# STM32.net
KiCad netlist of a schematic drawn in Altium Designer
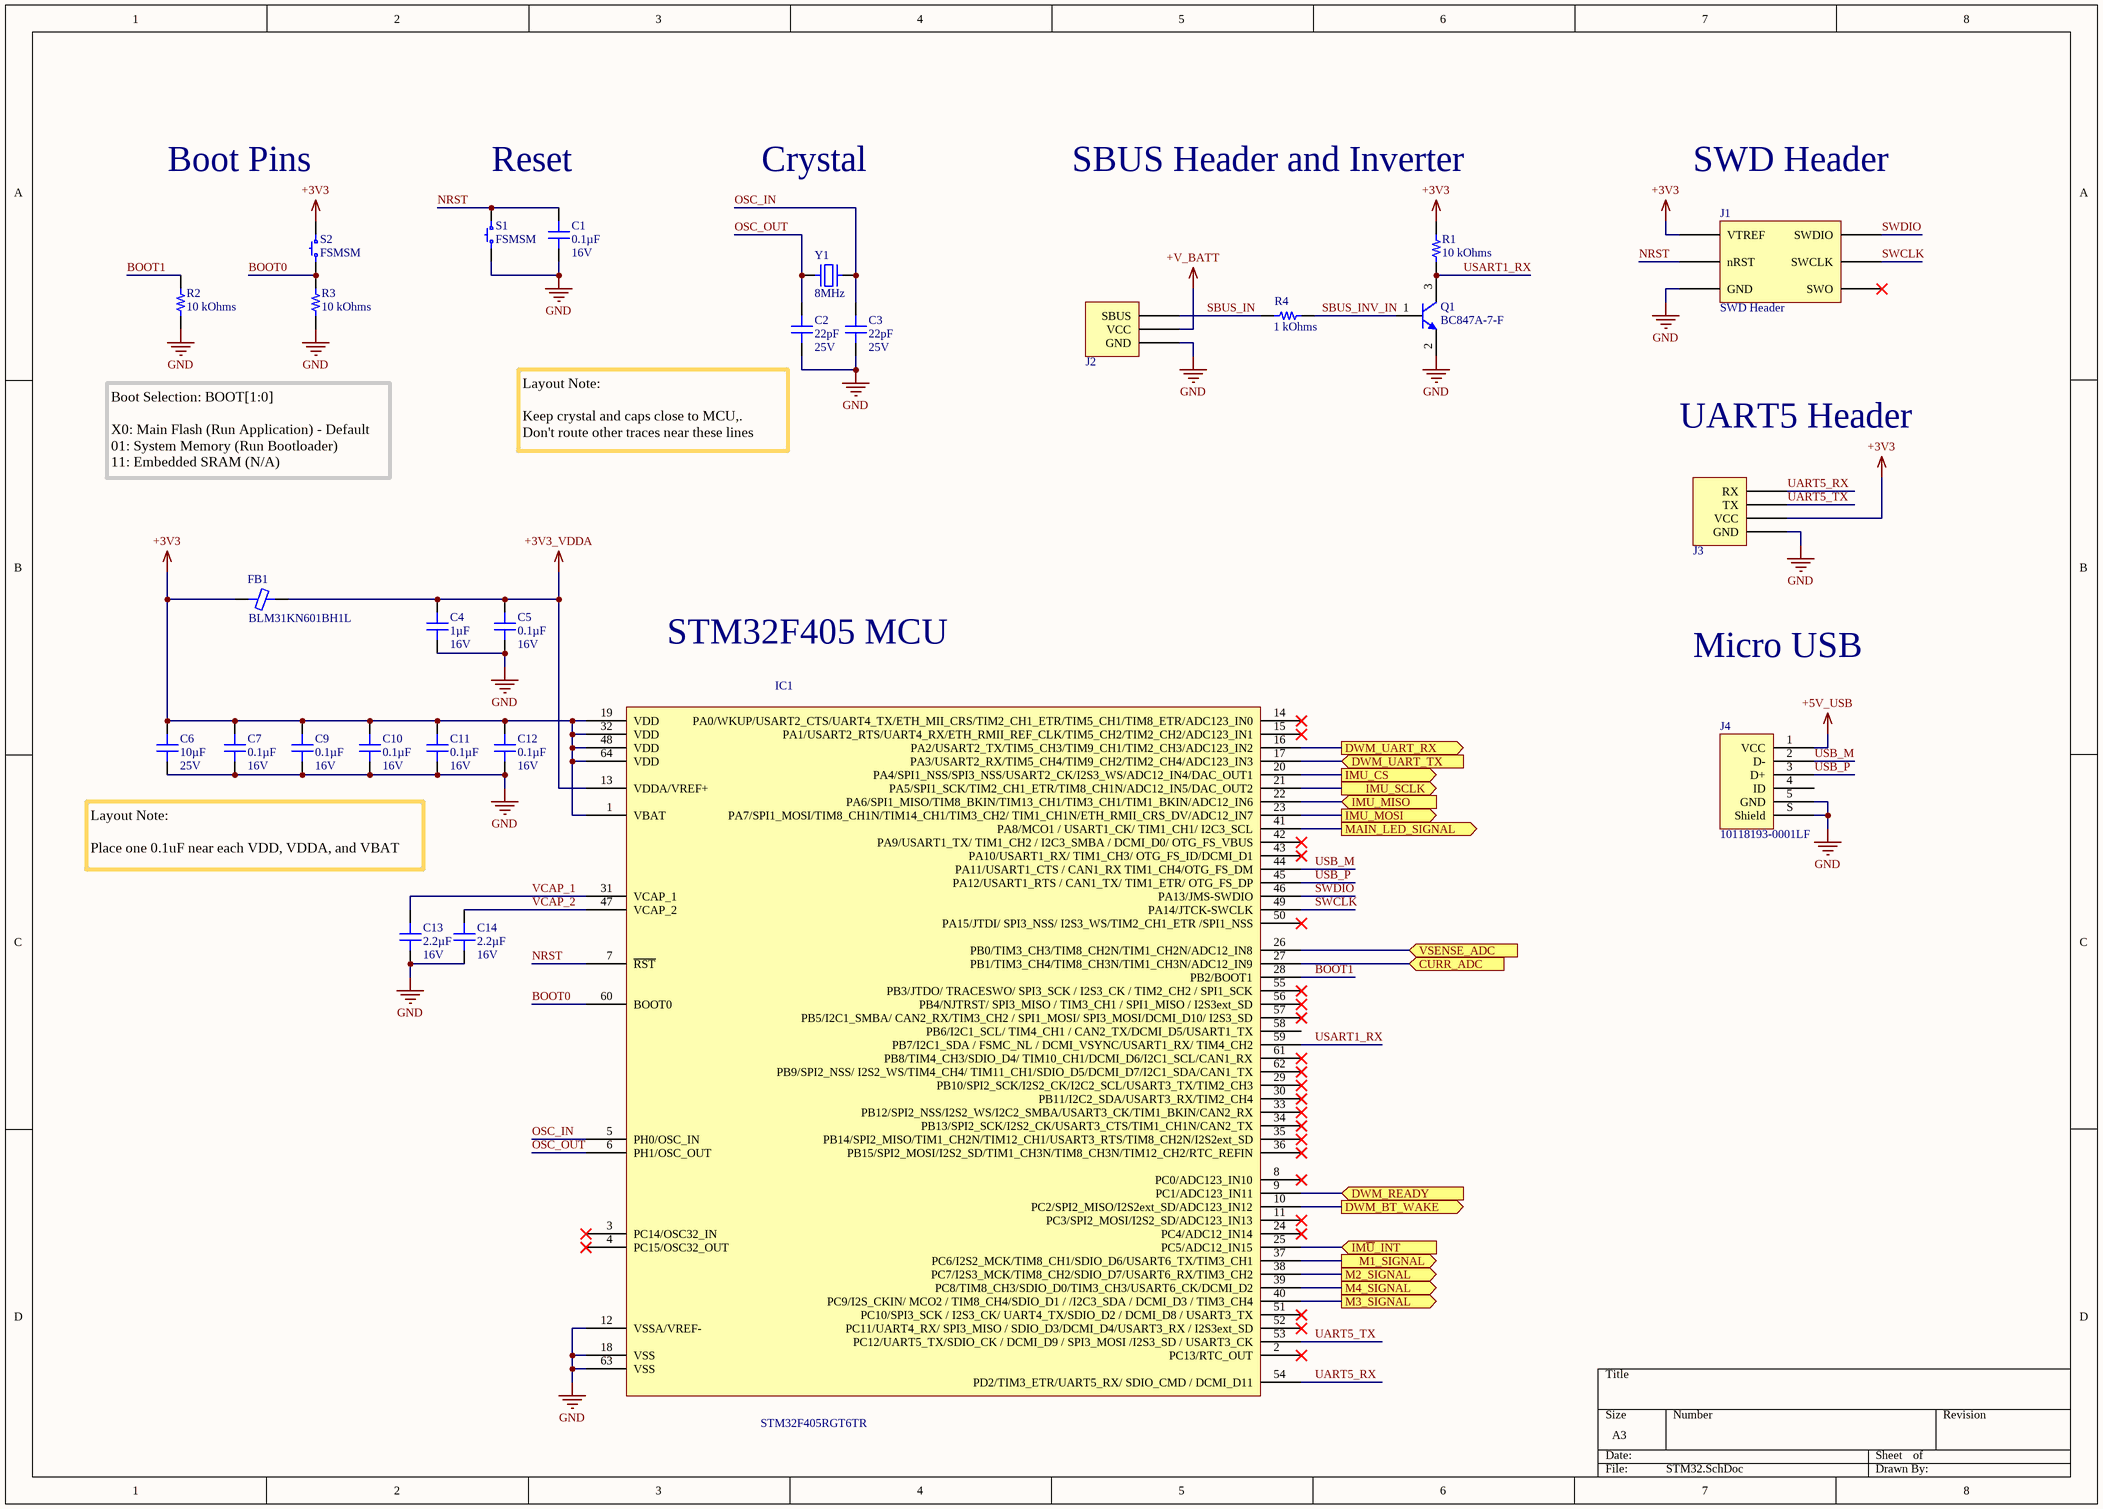
[diagram p0: STM32.SchDoc]

(export (version "E")
  (design (tool "Eeschema 10.0.6"))
  (components
    (comp (ref "C1")
      (value "0.1µF")
      (footprint "CAP 0603_1608")
      (description "CAP CER 0.1UF 16V X7R 0603")
      (fields
        (field (name "PART NUMBER") "CC0603KRX7R7BB104")
        (field (name "MANUFACTURER") "Yageo")
        (field (name "VOLTAGE - RATED") "16V")
      )
      (libsource (lib "Celestial Altium Library - altium_library") (part "Capacitor"))
    )
    (comp (ref "C2")
      (value "22pF")
      (footprint "CAP 0603_1608")
      (description "CAP CER 22PF 25V NPO 0603")
      (fields
        (field (name "PART NUMBER") "CC0603JRNPO8BN220")
        (field (name "MANUFACTURER") "Yageo")
        (field (name "VOLTAGE - RATED") "25V")
      )
      (libsource (lib "Celestial Altium Library - altium_library") (part "Capacitor"))
    )
    (comp (ref "C3")
      (value "22pF")
      (footprint "CAP 0603_1608")
      (description "CAP CER 22PF 25V NPO 0603")
      (fields
        (field (name "PART NUMBER") "CC0603JRNPO8BN220")
        (field (name "MANUFACTURER") "Yageo")
        (field (name "VOLTAGE - RATED") "25V")
      )
      (libsource (lib "Celestial Altium Library - altium_library") (part "Capacitor"))
    )
    (comp (ref "C4")
      (value "1µF")
      (footprint "CAP 0603_1608")
      (description "CAP CER 1UF 16V X5R 0603")
      (fields
        (field (name "PART NUMBER") "CC0603MRX5R7BB105")
        (field (name "MANUFACTURER") "Yageo")
        (field (name "VOLTAGE - RATED") "16V")
      )
      (libsource (lib "Celestial Altium Library - altium_library") (part "Capacitor"))
    )
    (comp (ref "C5")
      (value "0.1µF")
      (footprint "CAP 0603_1608")
      (description "CAP CER 0.1UF 16V X7R 0603")
      (fields
        (field (name "PART NUMBER") "CC0603KRX7R7BB104")
        (field (name "MANUFACTURER") "Yageo")
        (field (name "VOLTAGE - RATED") "16V")
      )
      (libsource (lib "Celestial Altium Library - altium_library") (part "Capacitor"))
    )
    (comp (ref "C6")
      (value "10µF")
      (footprint "CAP 0603_1608")
      (description "CAP CER 10UF 25V X5R 0603")
      (fields
        (field (name "PART NUMBER") "CC0603MRX5R8BB106")
        (field (name "MANUFACTURER") "Yageo")
        (field (name "VOLTAGE - RATED") "25V")
      )
      (libsource (lib "Celestial Altium Library - altium_library") (part "Capacitor"))
    )
    (comp (ref "C7")
      (value "0.1µF")
      (footprint "CAP 0603_1608")
      (description "CAP CER 0.1UF 16V X7R 0603")
      (fields
        (field (name "PART NUMBER") "CC0603KRX7R7BB104")
        (field (name "MANUFACTURER") "Yageo")
        (field (name "VOLTAGE - RATED") "16V")
      )
      (libsource (lib "Celestial Altium Library - altium_library") (part "Capacitor"))
    )
    (comp (ref "C9")
      (value "0.1µF")
      (footprint "CAP 0603_1608")
      (description "CAP CER 0.1UF 16V X7R 0603")
      (fields
        (field (name "PART NUMBER") "CC0603KRX7R7BB104")
        (field (name "MANUFACTURER") "Yageo")
        (field (name "VOLTAGE - RATED") "16V")
      )
      (libsource (lib "Celestial Altium Library - altium_library") (part "Capacitor"))
    )
    (comp (ref "C10")
      (value "0.1µF")
      (footprint "CAP 0603_1608")
      (description "CAP CER 0.1UF 16V X7R 0603")
      (fields
        (field (name "PART NUMBER") "CC0603KRX7R7BB104")
        (field (name "MANUFACTURER") "Yageo")
        (field (name "VOLTAGE - RATED") "16V")
      )
      (libsource (lib "Celestial Altium Library - altium_library") (part "Capacitor"))
    )
    (comp (ref "C11")
      (value "0.1µF")
      (footprint "CAP 0603_1608")
      (description "CAP CER 0.1UF 16V X7R 0603")
      (fields
        (field (name "PART NUMBER") "CC0603KRX7R7BB104")
        (field (name "MANUFACTURER") "Yageo")
        (field (name "VOLTAGE - RATED") "16V")
      )
      (libsource (lib "Celestial Altium Library - altium_library") (part "Capacitor"))
    )
    (comp (ref "C12")
      (value "0.1µF")
      (footprint "CAP 0603_1608")
      (description "CAP CER 0.1UF 16V X7R 0603")
      (fields
        (field (name "PART NUMBER") "CC0603KRX7R7BB104")
        (field (name "MANUFACTURER") "Yageo")
        (field (name "VOLTAGE - RATED") "16V")
      )
      (libsource (lib "Celestial Altium Library - altium_library") (part "Capacitor"))
    )
    (comp (ref "C13")
      (value "2.2µF")
      (footprint "CAP 0603_1608")
      (description "CAP CER 2.2UF 16V X5R 0603")
      (fields
        (field (name "PART NUMBER") "CC0603KRX5R7BB225")
        (field (name "MANUFACTURER") "Yageo")
        (field (name "VOLTAGE - RATED") "16V")
      )
      (libsource (lib "Celestial Altium Library - altium_library") (part "Capacitor"))
    )
    (comp (ref "C14")
      (value "2.2µF")
      (footprint "CAP 0603_1608")
      (description "CAP CER 2.2UF 16V X5R 0603")
      (fields
        (field (name "PART NUMBER") "CC0603KRX5R7BB225")
        (field (name "MANUFACTURER") "Yageo")
        (field (name "VOLTAGE - RATED") "16V")
      )
      (libsource (lib "Celestial Altium Library - altium_library") (part "Capacitor"))
    )
    (comp (ref "FB1")
      (value "BLM31KN601BH1L")
      (footprint "FER 1206_3216")
      (description "600OHM DCR MAX 2) A RATED CURREN")
      (fields
        (field (name "PART NUMBER") "BLM31KN601BH1L")
        (field (name "MANUFACTURER") "Murata Electronics")
      )
      (libsource (lib "Celestial Altium Library - altium_library") (part "Ferrite Chip"))
    )
    (comp (ref "IC1")
      (value "STM32F405RGT6TR")
      (footprint "ST LQFP-64 10X10MM")
      (description "IC MCU 32BIT 1MB FLASH 64LQFP")
      (fields (field (name "MANUFACTURER") "STMicroelectronics"))
      (libsource (lib "Celestial Altium Library - altium_library") (part "ST STM32F405RGT6 64PIN"))
    )
    (comp (ref "J1")
      (value "SWD Header")
      (footprint "SWD Header")
      (libsource (lib "Drone") (part "SWD Header"))
    )
    (comp (ref "J2")
      (value "SBUS Header")
      (footprint "SBUS Header")
      (libsource (lib "Drone") (part "SBUS Header"))
    )
    (comp (ref "J3")
      (value "UART Header")
      (footprint "UART Header")
      (libsource (lib "Drone") (part "UART Header"))
    )
    (comp (ref "J4")
      (value "10118193-0001LF")
      (footprint "FCI USB 10118193-0001LF")
      (description "CONN RCPT USB2.0 MICRO B SMD R/A")
      (fields (field (name "MANUFACTURER") "Amphenol ICC (FCI)"))
      (libsource (lib "Celestial Altium Library - altium_library") (part "USB 2.0 Type B Micro"))
    )
    (comp (ref "Q1")
      (value "BC847A-7-F")
      (footprint "DIODES SOT-23-3")
      (description "TRANS NPN 45V 0.1A SOT23-3")
      (fields (field (name "MANUFACTURER") "Diodes Incorporated"))
      (libsource (lib "Celestial Altium Library - altium_library") (part "DIODES INC NPN SOT-23-3"))
    )
    (comp (ref "R1")
      (value "10 kOhms")
      (footprint "RES 0603_1608")
      (description "RES SMD 10K OHM 1% 1/10W 0603")
      (fields (field (name "PART NUMBER") "AC0603FR-0710KL") (field (name "MANUFACTURER") "Yageo"))
      (libsource (lib "Celestial Altium Library - altium_library") (part "Resistor"))
    )
    (comp (ref "R2")
      (value "10 kOhms")
      (footprint "RES 0603_1608")
      (description "RES SMD 10K OHM 1% 1/10W 0603")
      (fields (field (name "PART NUMBER") "AC0603FR-0710KL") (field (name "MANUFACTURER") "Yageo"))
      (libsource (lib "Celestial Altium Library - altium_library") (part "Resistor"))
    )
    (comp (ref "R3")
      (value "10 kOhms")
      (footprint "RES 0603_1608")
      (description "RES SMD 10K OHM 1% 1/10W 0603")
      (fields (field (name "PART NUMBER") "AC0603FR-0710KL") (field (name "MANUFACTURER") "Yageo"))
      (libsource (lib "Celestial Altium Library - altium_library") (part "Resistor"))
    )
    (comp (ref "R4")
      (value "1 kOhms")
      (footprint "RES 0603_1608")
      (description "RES SMD 1K OHM 1% 1/10W 0603")
      (fields (field (name "PART NUMBER") "AC0603FR-071KL") (field (name "MANUFACTURER") "Yageo"))
      (libsource (lib "Celestial Altium Library - altium_library") (part "Resistor"))
    )
    (comp (ref "S1")
      (value "FSMSM")
      (footprint "TE FSMSMTR")
      (description "SWITCH TACTILE SPST-NO 0.05A 24V")
      (fields (field (name "MANUFACTURER") "TE Connectivity ALCOSWITCH Switches"))
      (libsource (lib "Celestial Altium Library - altium_library") (part "SPST-NO 2 PIN"))
    )
    (comp (ref "S2")
      (value "FSMSM")
      (footprint "TE FSMSMTR")
      (description "SWITCH TACTILE SPST-NO 0.05A 24V")
      (fields (field (name "MANUFACTURER") "TE Connectivity ALCOSWITCH Switches"))
      (libsource (lib "Celestial Altium Library - altium_library") (part "SPST-NO 2 PIN"))
    )
    (comp (ref "Y1")
      (value "8MHz")
      (footprint "ABRACON ABLS")
      (description "CRYSTAL 8.0000MHZ 16PF SMD")
      (fields
        (field (name "PART NUMBER") "ABLS-8.000MHZ-16-A-4-H-T")
        (field (name "MANUFACTURER") "Abracon LLC")
      )
      (libsource (lib "Celestial Altium Library - altium_library") (part "Abracon Crystal ABLS"))
    )
  )
  (nets
    (net (code "1") (name "+3V3") (class "Default")
      (node (ref "C10") (pin "2") (pinfunction "2_2") (pintype "passive"))
      (node (ref "C11") (pin "2") (pinfunction "2_2") (pintype "passive"))
      (node (ref "C12") (pin "2") (pinfunction "2_2") (pintype "passive"))
      (node (ref "C6") (pin "2") (pinfunction "2_2") (pintype "passive"))
      (node (ref "C7") (pin "2") (pinfunction "2_2") (pintype "passive"))
      (node (ref "C9") (pin "2") (pinfunction "2_2") (pintype "passive"))
      (node (ref "FB1") (pin "1") (pinfunction "1_1") (pintype "passive"))
      (node (ref "IC1") (pin "1") (pinfunction "VBAT_1") (pintype "passive"))
      (node (ref "IC1") (pin "19") (pinfunction "VDD_19") (pintype "passive"))
      (node (ref "IC1") (pin "32") (pinfunction "VDD_32") (pintype "passive"))
      (node (ref "IC1") (pin "48") (pinfunction "VDD_48") (pintype "passive"))
      (node (ref "IC1") (pin "64") (pinfunction "VDD_64") (pintype "passive"))
      (node (ref "J1") (pin "VTREF") (pinfunction "VTREF_VTREF") (pintype "passive"))
      (node (ref "J3") (pin "VCC") (pinfunction "VCC_VCC") (pintype "passive"))
      (node (ref "R1") (pin "2") (pinfunction "2_2") (pintype "passive"))
      (node (ref "S2") (pin "2") (pinfunction "2_2") (pintype "passive"))
    )
    (net (code "2") (name "+3V3_VDDA") (class "Default")
      (node (ref "C4") (pin "2") (pinfunction "2_2") (pintype "passive"))
      (node (ref "C5") (pin "2") (pinfunction "2_2") (pintype "passive"))
      (node (ref "FB1") (pin "2") (pinfunction "2_2") (pintype "passive"))
      (node (ref "IC1") (pin "13") (pinfunction "VDDA/VREF+_13") (pintype "passive"))
    )
    (net (code "3") (name "+5V_USB") (class "Default")
      (node (ref "J4") (pin "1") (pinfunction "VCC_1") (pintype "passive"))
    )
    (net (code "4") (name "+V_BATT") (class "Default")
      (node (ref "J2") (pin "VCC") (pinfunction "VCC_VCC") (pintype "passive"))
    )
    (net (code "5") (name "/BOOT0") (class "Default")
      (node (ref "IC1") (pin "60") (pinfunction "BOOT0_60") (pintype "passive"))
      (node (ref "R3") (pin "2") (pinfunction "2_2") (pintype "passive"))
      (node (ref "S2") (pin "1") (pinfunction "1_1") (pintype "passive"))
    )
    (net (code "6") (name "/BOOT1") (class "Default")
      (node (ref "IC1") (pin "28") (pinfunction "PB2/BOOT1_28") (pintype "passive"))
      (node (ref "R2") (pin "2") (pinfunction "2_2") (pintype "passive"))
    )
    (net (code "7") (name "/CURR_ADC") (class "Default")
      (node (ref "IC1") (pin "27") (pinfunction "PB1/TIM3_CH4/TIM8_CH3N/TIM1_CH3N/ADC12_IN9_27") (pintype "passive"))
    )
    (net (code "8") (name "/DWM_BT_WAKE") (class "Default")
      (node (ref "IC1") (pin "10") (pinfunction "PC2/SPI2_MISO/I2S2ext_SD/ADC123_IN12_10") (pintype "passive"))
    )
    (net (code "9") (name "/DWM_READY") (class "Default")
      (node (ref "IC1") (pin "9") (pinfunction "PC1/ADC123_IN11_9") (pintype "passive"))
    )
    (net (code "10") (name "/DWM_UART_RX") (class "Default")
      (node (ref "IC1") (pin "16") (pinfunction "PA2/USART2_TX/TIM5_CH3/TIM9_CH1/TIM2_CH3/ADC123_IN2_16") (pintype "passive"))
    )
    (net (code "11") (name "/DWM_UART_TX") (class "Default")
      (node (ref "IC1") (pin "17") (pinfunction "PA3/USART2_RX/TIM5_CH4/TIM9_CH2/TIM2_CH4/ADC123_IN3_17") (pintype "passive"))
    )
    (net (code "12") (name "/IMU_CS") (class "Default")
      (node (ref "IC1") (pin "20") (pinfunction "PA4/SPI1_NSS/SPI3_NSS/USART2_CK/I2S3_WS/ADC12_IN4/DAC_OUT1_20") (pintype "passive"))
    )
    (net (code "13") (name "/IMU_MISO") (class "Default")
      (node (ref "IC1") (pin "22") (pinfunction "PA6/SPI1_MISO/TIM8_BKIN/TIM13_CH1/TIM3_CH1/TIM1_BKIN/ADC12_IN6_22") (pintype "passive"))
    )
    (net (code "14") (name "/IMU_MOSI") (class "Default")
      (node (ref "IC1") (pin "23") (pinfunction "PA7/SPI1_MOSI/TIM8_CH1N/TIM14_CH1/TIM3_CH2/_TIM1_CH1N/ETH_RMII_CRS_DV/ADC12_IN7_23") (pintype "passive"))
    )
    (net (code "15") (name "/IMU_SCLK") (class "Default")
      (node (ref "IC1") (pin "21") (pinfunction "PA5/SPI1_SCK/TIM2_CH1_ETR/TIM8_CH1N/ADC12_IN5/DAC_OUT2_21") (pintype "passive"))
    )
    (net (code "16") (name "/IM~{U}_INT") (class "Default")
      (node (ref "IC1") (pin "25") (pinfunction "PC5/ADC12_IN15_25") (pintype "passive"))
    )
    (net (code "17") (name "/M1_SIGNAL") (class "Default")
      (node (ref "IC1") (pin "37") (pinfunction "PC6/I2S2_MCK/TIM8_CH1/SDIO_D6/USART6_TX/TIM3_CH1_37") (pintype "passive"))
    )
    (net (code "18") (name "/M2_SIGNAL") (class "Default")
      (node (ref "IC1") (pin "38") (pinfunction "PC7/I2S3_MCK/TIM8_CH2/SDIO_D7/USART6_RX/TIM3_CH2_38") (pintype "passive"))
    )
    (net (code "19") (name "/M3_SIGNAL") (class "Default")
      (node (ref "IC1") (pin "40") (pinfunction "PC9/I2S_CKIN/_MCO2_/_TIM8_CH4/SDIO_D1_/_/I2C3_SDA_/_DCMI_D3_/_TIM3_CH4_40") (pintype "passive"))
    )
    (net (code "20") (name "/M4_SIGNAL") (class "Default")
      (node (ref "IC1") (pin "39") (pinfunction "PC8/TIM8_CH3/SDIO_D0/TIM3_CH3/USART6_CK/DCMI_D2_39") (pintype "passive"))
    )
    (net (code "21") (name "/MAIN_LED_SIGNAL") (class "Default")
      (node (ref "IC1") (pin "41") (pinfunction "PA8/MCO1_/_USART1_CK/_TIM1_CH1/_I2C3_SCL_41") (pintype "passive"))
    )
    (net (code "22") (name "/NRST") (class "Default")
      (node (ref "C1") (pin "2") (pinfunction "2_2") (pintype "passive"))
      (node (ref "IC1") (pin "7") (pinfunction "~{RST}_7") (pintype "passive"))
      (node (ref "J1") (pin "nRST") (pinfunction "nRST_nRST") (pintype "passive"))
      (node (ref "S1") (pin "2") (pinfunction "2_2") (pintype "passive"))
    )
    (net (code "23") (name "/OSC_IN") (class "Default")
      (node (ref "C3") (pin "2") (pinfunction "2_2") (pintype "passive"))
      (node (ref "IC1") (pin "5") (pinfunction "PH0/OSC_IN_5") (pintype "passive"))
      (node (ref "Y1") (pin "1") (pinfunction "1_1") (pintype "passive"))
    )
    (net (code "24") (name "/OSC_OUT") (class "Default")
      (node (ref "C2") (pin "2") (pinfunction "2_2") (pintype "passive"))
      (node (ref "IC1") (pin "6") (pinfunction "PH1/OSC_OUT_6") (pintype "passive"))
      (node (ref "Y1") (pin "2") (pinfunction "2_2") (pintype "passive"))
    )
    (net (code "25") (name "/SBUS_IN") (class "Default")
      (node (ref "J2") (pin "SBUS") (pinfunction "SBUS_SBUS") (pintype "passive"))
      (node (ref "R4") (pin "1") (pinfunction "1_1") (pintype "passive"))
    )
    (net (code "26") (name "/SBUS_INV_IN") (class "Default")
      (node (ref "Q1") (pin "1") (pinfunction "B_1") (pintype "passive"))
      (node (ref "R4") (pin "2") (pinfunction "2_2") (pintype "passive"))
    )
    (net (code "27") (name "/SWCLK") (class "Default")
      (node (ref "IC1") (pin "49") (pinfunction "PA14/JTCK-SWCLK_49") (pintype "passive"))
      (node (ref "J1") (pin "SWCLK") (pinfunction "SWCLK_SWCLK") (pintype "passive"))
    )
    (net (code "28") (name "/SWDIO") (class "Default")
      (node (ref "IC1") (pin "46") (pinfunction "PA13/JMS-SWDIO_46") (pintype "passive"))
      (node (ref "J1") (pin "SWDIO") (pinfunction "SWDIO_SWDIO") (pintype "passive"))
    )
    (net (code "29") (name "/UART5_RX") (class "Default")
      (node (ref "IC1") (pin "54") (pinfunction "PD2/TIM3_ETR/UART5_RX/_SDIO_CMD_/_DCMI_D11_54") (pintype "passive"))
      (node (ref "J3") (pin "RX") (pinfunction "RX_RX") (pintype "passive"))
    )
    (net (code "30") (name "/UART5_TX") (class "Default")
      (node (ref "IC1") (pin "53") (pinfunction "PC12/UART5_TX/SDIO_CK_/_DCMI_D9_/_SPI3_MOSI_/I2S3_SD_/_USART3_CK_53") (pintype "passive"))
      (node (ref "J3") (pin "TX") (pinfunction "TX_TX") (pintype "passive"))
    )
    (net (code "31") (name "/USART1_RX") (class "Default")
      (node (ref "IC1") (pin "59") (pinfunction "PB7/I2C1_SDA_/_FSMC_NL_/_DCMI_VSYNC/USART1_RX/_TIM4_CH2_59") (pintype "passive"))
      (node (ref "Q1") (pin "3") (pinfunction "C_3") (pintype "passive"))
      (node (ref "R1") (pin "1") (pinfunction "1_1") (pintype "passive"))
    )
    (net (code "32") (name "/USB_M") (class "Default")
      (node (ref "IC1") (pin "44") (pinfunction "PA11/USART1_CTS_/_CAN1_RX_TIM1_CH4/OTG_FS_DM_44") (pintype "passive"))
      (node (ref "J4") (pin "2") (pinfunction "D-_2") (pintype "passive"))
    )
    (net (code "33") (name "/USB_P") (class "Default")
      (node (ref "IC1") (pin "45") (pinfunction "PA12/USART1_RTS_/_CAN1_TX/_TIM1_ETR/_OTG_FS_DP_45") (pintype "passive"))
      (node (ref "J4") (pin "3") (pinfunction "D+_3") (pintype "passive"))
    )
    (net (code "34") (name "/VCAP_1") (class "Default")
      (node (ref "C13") (pin "2") (pinfunction "2_2") (pintype "passive"))
      (node (ref "IC1") (pin "31") (pinfunction "VCAP_1_31") (pintype "passive"))
    )
    (net (code "35") (name "/VCAP_2") (class "Default")
      (node (ref "C14") (pin "2") (pinfunction "2_2") (pintype "passive"))
      (node (ref "IC1") (pin "47") (pinfunction "VCAP_2_47") (pintype "passive"))
    )
    (net (code "36") (name "/VSENSE_ADC") (class "Default")
      (node (ref "IC1") (pin "26") (pinfunction "PB0/TIM3_CH3/TIM8_CH2N/TIM1_CH2N/ADC12_IN8_26") (pintype "passive"))
    )
    (net (code "37") (name "GND") (class "Default")
      (node (ref "C1") (pin "1") (pinfunction "1_1") (pintype "passive"))
      (node (ref "C10") (pin "1") (pinfunction "1_1") (pintype "passive"))
      (node (ref "C11") (pin "1") (pinfunction "1_1") (pintype "passive"))
      (node (ref "C12") (pin "1") (pinfunction "1_1") (pintype "passive"))
      (node (ref "C13") (pin "1") (pinfunction "1_1") (pintype "passive"))
      (node (ref "C14") (pin "1") (pinfunction "1_1") (pintype "passive"))
      (node (ref "C2") (pin "1") (pinfunction "1_1") (pintype "passive"))
      (node (ref "C3") (pin "1") (pinfunction "1_1") (pintype "passive"))
      (node (ref "C4") (pin "1") (pinfunction "1_1") (pintype "passive"))
      (node (ref "C5") (pin "1") (pinfunction "1_1") (pintype "passive"))
      (node (ref "C6") (pin "1") (pinfunction "1_1") (pintype "passive"))
      (node (ref "C7") (pin "1") (pinfunction "1_1") (pintype "passive"))
      (node (ref "C9") (pin "1") (pinfunction "1_1") (pintype "passive"))
      (node (ref "IC1") (pin "12") (pinfunction "VSSA/VREF-_12") (pintype "passive"))
      (node (ref "IC1") (pin "18") (pinfunction "VSS_18") (pintype "passive"))
      (node (ref "IC1") (pin "63") (pinfunction "VSS_63") (pintype "passive"))
      (node (ref "J1") (pin "GND") (pinfunction "GND_GND") (pintype "passive"))
      (node (ref "J2") (pin "GND") (pinfunction "GND_GND") (pintype "passive"))
      (node (ref "J3") (pin "GND") (pinfunction "GND_GND") (pintype "passive"))
      (node (ref "J4") (pin "5") (pinfunction "GND_5") (pintype "passive"))
      (node (ref "J4") (pin "S") (pinfunction "Shield_S") (pintype "passive"))
      (node (ref "Q1") (pin "2") (pinfunction "E_2") (pintype "passive"))
      (node (ref "R2") (pin "1") (pinfunction "1_1") (pintype "passive"))
      (node (ref "R3") (pin "1") (pinfunction "1_1") (pintype "passive"))
      (node (ref "S1") (pin "1") (pinfunction "1_1") (pintype "passive"))
    )
    (net (code "38") (name "unconnected-(IC1-PA0{slash}WKUP{slash}USART2_CTS{slash}UART4_TX{slash}ETH_MII_CRS{slash}TIM2_CH1_ETR{slash}TIM5_CH1{slash}TIM8_ETR{slash}ADC123_IN0-Pad14)") (class "Default")
      (node (ref "IC1") (pin "14") (pinfunction "PA0/WKUP/USART2_CTS/UART4_TX/ETH_MII_CRS/TIM2_CH1_ETR/TIM5_CH1/TIM8_ETR/ADC123_IN0_14") (pintype "passive+no_connect"))
    )
    (net (code "39") (name "unconnected-(IC1-PA1{slash}USART2_RTS{slash}UART4_RX{slash}ETH_RMII_REF_CLK{slash}TIM5_CH2{slash}TIM2_CH2{slash}ADC123_IN1-Pad15)") (class "Default")
      (node (ref "IC1") (pin "15") (pinfunction "PA1/USART2_RTS/UART4_RX/ETH_RMII_REF_CLK/TIM5_CH2/TIM2_CH2/ADC123_IN1_15") (pintype "passive+no_connect"))
    )
    (net (code "40") (name "unconnected-(IC1-PA9{slash}USART1_TX{slash}_TIM1_CH2_{slash}_I2C3_SMBA_{slash}_DCMI_D0{slash}_OTG_FS_VBUS-Pad42)") (class "Default")
      (node (ref "IC1") (pin "42") (pinfunction "PA9/USART1_TX/_TIM1_CH2_/_I2C3_SMBA_/_DCMI_D0/_OTG_FS_VBUS_42") (pintype "passive+no_connect"))
    )
    (net (code "41") (name "unconnected-(IC1-PA10{slash}USART1_RX{slash}_TIM1_CH3{slash}_OTG_FS_ID{slash}DCMI_D1-Pad43)") (class "Default")
      (node (ref "IC1") (pin "43") (pinfunction "PA10/USART1_RX/_TIM1_CH3/_OTG_FS_ID/DCMI_D1_43") (pintype "passive+no_connect"))
    )
    (net (code "42") (name "unconnected-(IC1-PA15{slash}JTDI{slash}_SPI3_NSS{slash}_I2S3_WS{slash}TIM2_CH1_ETR_{slash}SPI1_NSS-Pad50)") (class "Default")
      (node (ref "IC1") (pin "50") (pinfunction "PA15/JTDI/_SPI3_NSS/_I2S3_WS/TIM2_CH1_ETR_/SPI1_NSS_50") (pintype "passive+no_connect"))
    )
    (net (code "43") (name "unconnected-(IC1-PB3{slash}JTDO{slash}_TRACESWO{slash}_SPI3_SCK_{slash}_I2S3_CK_{slash}_TIM2_CH2_{slash}_SPI1_SCK-Pad55)") (class "Default")
      (node (ref "IC1") (pin "55") (pinfunction "PB3/JTDO/_TRACESWO/_SPI3_SCK_/_I2S3_CK_/_TIM2_CH2_/_SPI1_SCK_55") (pintype "passive+no_connect"))
    )
    (net (code "44") (name "unconnected-(IC1-PB4{slash}NJTRST{slash}_SPI3_MISO_{slash}_TIM3_CH1_{slash}_SPI1_MISO_{slash}_I2S3ext_SD-Pad56)") (class "Default")
      (node (ref "IC1") (pin "56") (pinfunction "PB4/NJTRST/_SPI3_MISO_/_TIM3_CH1_/_SPI1_MISO_/_I2S3ext_SD_56") (pintype "passive+no_connect"))
    )
    (net (code "45") (name "unconnected-(IC1-PB5{slash}I2C1_SMBA{slash}_CAN2_RX{slash}TIM3_CH2_{slash}_SPI1_MOSI{slash}_SPI3_MOSI{slash}DCMI_D10{slash}_I2S3_SD-Pad57)") (class "Default")
      (node (ref "IC1") (pin "57") (pinfunction "PB5/I2C1_SMBA/_CAN2_RX/TIM3_CH2_/_SPI1_MOSI/_SPI3_MOSI/DCMI_D10/_I2S3_SD_57") (pintype "passive+no_connect"))
    )
    (net (code "46") (name "unconnected-(IC1-PB6{slash}I2C1_SCL{slash}_TIM4_CH1_{slash}_CAN2_TX{slash}DCMI_D5{slash}USART1_TX-Pad58)") (class "Default")
      (node (ref "IC1") (pin "58") (pinfunction "PB6/I2C1_SCL/_TIM4_CH1_/_CAN2_TX/DCMI_D5/USART1_TX_58") (pintype "passive"))
    )
    (net (code "47") (name "unconnected-(IC1-PB8{slash}TIM4_CH3{slash}SDIO_D4{slash}_TIM10_CH1{slash}DCMI_D6{slash}I2C1_SCL{slash}CAN1_RX-Pad61)") (class "Default")
      (node (ref "IC1") (pin "61") (pinfunction "PB8/TIM4_CH3/SDIO_D4/_TIM10_CH1/DCMI_D6/I2C1_SCL/CAN1_RX_61") (pintype "passive+no_connect"))
    )
    (net (code "48") (name "unconnected-(IC1-PB9{slash}SPI2_NSS{slash}_I2S2_WS{slash}TIM4_CH4{slash}_TIM11_CH1{slash}SDIO_D5{slash}DCMI_D7{slash}I2C1_SDA{slash}CAN1_TX-Pad62)") (class "Default")
      (node (ref "IC1") (pin "62") (pinfunction "PB9/SPI2_NSS/_I2S2_WS/TIM4_CH4/_TIM11_CH1/SDIO_D5/DCMI_D7/I2C1_SDA/CAN1_TX_62") (pintype "passive+no_connect"))
    )
    (net (code "49") (name "unconnected-(IC1-PB10{slash}SPI2_SCK{slash}I2S2_CK{slash}I2C2_SCL{slash}USART3_TX{slash}TIM2_CH3-Pad29)") (class "Default")
      (node (ref "IC1") (pin "29") (pinfunction "PB10/SPI2_SCK/I2S2_CK/I2C2_SCL/USART3_TX/TIM2_CH3_29") (pintype "passive+no_connect"))
    )
    (net (code "50") (name "unconnected-(IC1-PB11{slash}I2C2_SDA{slash}USART3_RX{slash}TIM2_CH4-Pad30)") (class "Default")
      (node (ref "IC1") (pin "30") (pinfunction "PB11/I2C2_SDA/USART3_RX/TIM2_CH4_30") (pintype "passive+no_connect"))
    )
    (net (code "51") (name "unconnected-(IC1-PB12{slash}SPI2_NSS{slash}I2S2_WS{slash}I2C2_SMBA{slash}USART3_CK{slash}TIM1_BKIN{slash}CAN2_RX-Pad33)") (class "Default")
      (node (ref "IC1") (pin "33") (pinfunction "PB12/SPI2_NSS/I2S2_WS/I2C2_SMBA/USART3_CK/TIM1_BKIN/CAN2_RX_33") (pintype "passive+no_connect"))
    )
    (net (code "52") (name "unconnected-(IC1-PB13{slash}SPI2_SCK{slash}I2S2_CK{slash}USART3_CTS{slash}TIM1_CH1N{slash}CAN2_TX-Pad34)") (class "Default")
      (node (ref "IC1") (pin "34") (pinfunction "PB13/SPI2_SCK/I2S2_CK/USART3_CTS/TIM1_CH1N/CAN2_TX_34") (pintype "passive+no_connect"))
    )
    (net (code "53") (name "unconnected-(IC1-PB14{slash}SPI2_MISO{slash}TIM1_CH2N{slash}TIM12_CH1{slash}USART3_RTS{slash}TIM8_CH2N{slash}I2S2ext_SD-Pad35)") (class "Default")
      (node (ref "IC1") (pin "35") (pinfunction "PB14/SPI2_MISO/TIM1_CH2N/TIM12_CH1/USART3_RTS/TIM8_CH2N/I2S2ext_SD_35") (pintype "passive+no_connect"))
    )
    (net (code "54") (name "unconnected-(IC1-PB15{slash}SPI2_MOSI{slash}I2S2_SD{slash}TIM1_CH3N{slash}TIM8_CH3N{slash}TIM12_CH2{slash}RTC_REFIN-Pad36)") (class "Default")
      (node (ref "IC1") (pin "36") (pinfunction "PB15/SPI2_MOSI/I2S2_SD/TIM1_CH3N/TIM8_CH3N/TIM12_CH2/RTC_REFIN_36") (pintype "passive+no_connect"))
    )
    (net (code "55") (name "unconnected-(IC1-PC0{slash}ADC123_IN10-Pad8)") (class "Default")
      (node (ref "IC1") (pin "8") (pinfunction "PC0/ADC123_IN10_8") (pintype "passive+no_connect"))
    )
    (net (code "56") (name "unconnected-(IC1-PC3{slash}SPI2_MOSI{slash}I2S2_SD{slash}ADC123_IN13-Pad11)") (class "Default")
      (node (ref "IC1") (pin "11") (pinfunction "PC3/SPI2_MOSI/I2S2_SD/ADC123_IN13_11") (pintype "passive+no_connect"))
    )
    (net (code "57") (name "unconnected-(IC1-PC4{slash}ADC12_IN14-Pad24)") (class "Default")
      (node (ref "IC1") (pin "24") (pinfunction "PC4/ADC12_IN14_24") (pintype "passive+no_connect"))
    )
    (net (code "58") (name "unconnected-(IC1-PC10{slash}SPI3_SCK_{slash}_I2S3_CK{slash}_UART4_TX{slash}SDIO_D2_{slash}_DCMI_D8_{slash}_USART3_TX-Pad51)") (class "Default")
      (node (ref "IC1") (pin "51") (pinfunction "PC10/SPI3_SCK_/_I2S3_CK/_UART4_TX/SDIO_D2_/_DCMI_D8_/_USART3_TX_51") (pintype "passive+no_connect"))
    )
    (net (code "59") (name "unconnected-(IC1-PC11{slash}UART4_RX{slash}_SPI3_MISO_{slash}_SDIO_D3{slash}DCMI_D4{slash}USART3_RX_{slash}_I2S3ext_SD-Pad52)") (class "Default")
      (node (ref "IC1") (pin "52") (pinfunction "PC11/UART4_RX/_SPI3_MISO_/_SDIO_D3/DCMI_D4/USART3_RX_/_I2S3ext_SD_52") (pintype "passive+no_connect"))
    )
    (net (code "60") (name "unconnected-(IC1-PC13{slash}RTC_OUT-Pad2)") (class "Default")
      (node (ref "IC1") (pin "2") (pinfunction "PC13/RTC_OUT_2") (pintype "passive+no_connect"))
    )
    (net (code "61") (name "unconnected-(IC1-PC14{slash}OSC32_IN-Pad3)") (class "Default")
      (node (ref "IC1") (pin "3") (pinfunction "PC14/OSC32_IN_3") (pintype "passive+no_connect"))
    )
    (net (code "62") (name "unconnected-(IC1-PC15{slash}OSC32_OUT-Pad4)") (class "Default")
      (node (ref "IC1") (pin "4") (pinfunction "PC15/OSC32_OUT_4") (pintype "passive+no_connect"))
    )
    (net (code "63") (name "unconnected-(J1-PadSWO)") (class "Default")
      (node (ref "J1") (pin "SWO") (pinfunction "SWO_SWO") (pintype "passive+no_connect"))
    )
    (net (code "64") (name "unconnected-(J4-ID-Pad4)") (class "Default")
      (node (ref "J4") (pin "4") (pinfunction "ID_4") (pintype "passive"))
    )
  )
)
